# Z05_CC_SHIELD_02.net
KiCad netlist of a schematic drawn in EAGLE
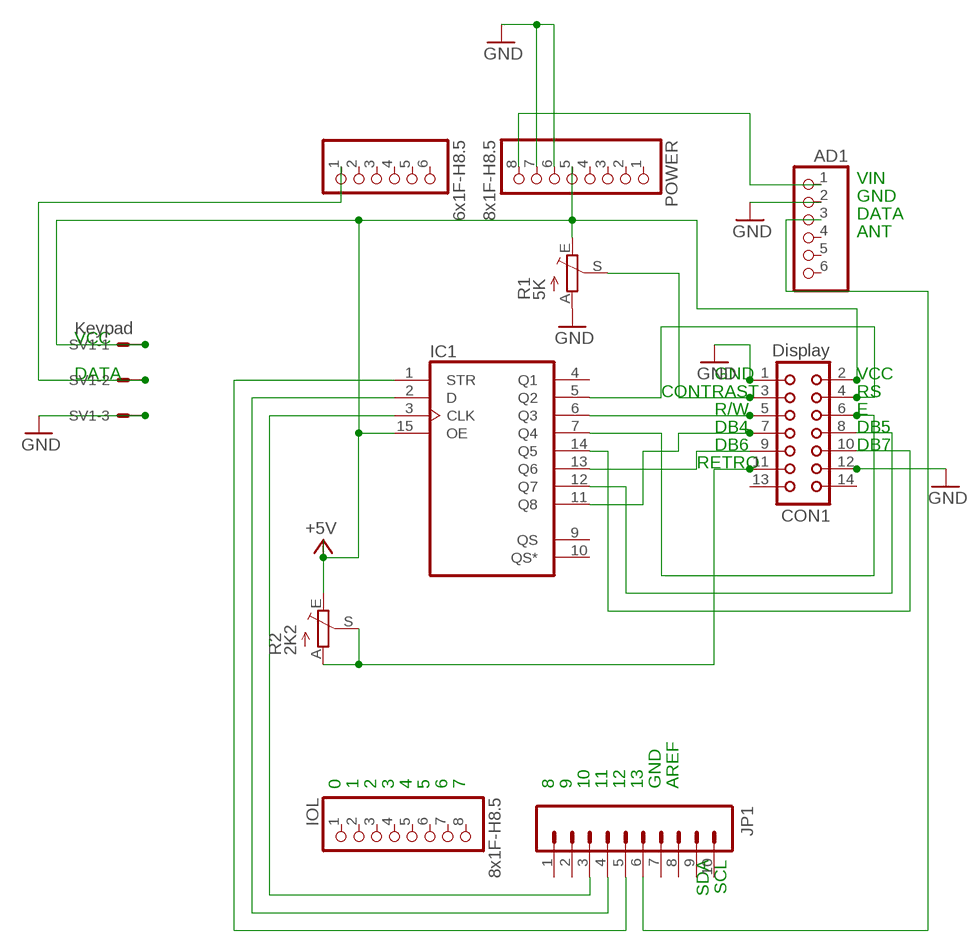
[diagram p0: schematic, sheet 1]

(export (version "E")
  (design (tool "Eeschema 10.0.6"))
  (components
    (comp (ref "AD")
      (value "6x1F-H8.5")
      (footprint "eagle-import:1X06")
      (libsource (lib "eagle-import") (part "PINHD-1X6"))
    )
    (comp (ref "AD1")
      (value "6x1F-H8.5")
      (footprint "eagle-import:1X06")
      (libsource (lib "eagle-import") (part "PINHD-1X6"))
    )
    (comp (ref "CON1")
      (value "Display")
      (footprint "eagle-import:CON14")
      (libsource (lib "eagle-import") (part "CON14"))
    )
    (comp (ref "IC1")
      (value "4094N")
      (footprint "eagle-import:DIL16")
      (libsource (lib "eagle-import") (part "4094N"))
    )
    (comp (ref "IOL")
      (value "8x1F-H8.5")
      (footprint "eagle-import:1X08")
      (libsource (lib "eagle-import") (part "PINHD-1X8"))
    )
    (comp (ref "JP1")
      (value "M10\"")
      (footprint "eagle-import:1X10")
      (libsource (lib "eagle-import") (part "M10{dblquote}"))
    )
    (comp (ref "POWER")
      (value "8x1F-H8.5")
      (footprint "eagle-import:1X08")
      (libsource (lib "eagle-import") (part "PINHD-1X8"))
    )
    (comp (ref "R1")
      (value "5K")
      (footprint "eagle-import:LI10")
      (libsource (lib "eagle-import") (part "TRIM_EU-LI10"))
    )
    (comp (ref "R2")
      (value "2K2")
      (footprint "eagle-import:LI10")
      (libsource (lib "eagle-import") (part "TRIM_EU-LI10"))
    )
    (comp (ref "SV1")
      (value "Keypad")
      (footprint "eagle-import:7395-05")
      (libsource (lib "eagle-import") (part "22-?-0505-7058"))
    )
  )
  (nets
    (net (code "1") (name "+5V") (class "Default")
      (node (ref "CON1") (pin "2") (pinfunction "2_2") (pintype "passive"))
      (node (ref "IC1") (pin "15") (pinfunction "OE_15") (pintype "input"))
      (node (ref "POWER") (pin "5") (pinfunction "5_5") (pintype "passive"))
      (node (ref "R1") (pin "E") (pinfunction "E_E") (pintype "passive"))
      (node (ref "R2") (pin "E") (pinfunction "E_E") (pintype "passive"))
      (node (ref "SV1") (pin "1") (pinfunction "S_1") (pintype "passive"))
    )
    (net (code "2") (name "GND") (class "Default")
      (node (ref "AD1") (pin "2") (pinfunction "2_2") (pintype "passive"))
      (node (ref "CON1") (pin "1") (pinfunction "1_1") (pintype "passive"))
      (node (ref "CON1") (pin "12") (pinfunction "12_12") (pintype "passive"))
      (node (ref "POWER") (pin "6") (pinfunction "6_6") (pintype "passive"))
      (node (ref "POWER") (pin "7") (pinfunction "7_7") (pintype "passive"))
      (node (ref "R1") (pin "A") (pinfunction "A_A") (pintype "passive"))
      (node (ref "SV1") (pin "3") (pinfunction "S_3") (pintype "passive"))
    )
    (net (code "3") (name "Net-(AD1-Pad1)") (class "Default")
      (node (ref "AD1") (pin "1") (pinfunction "1_1") (pintype "passive"))
      (node (ref "POWER") (pin "8") (pinfunction "8_8") (pintype "passive"))
    )
    (net (code "4") (name "Net-(AD1-Pad3)") (class "Default")
      (node (ref "AD1") (pin "3") (pinfunction "3_3") (pintype "passive"))
      (node (ref "JP1") (pin "6") (pinfunction "6_6") (pintype "passive"))
    )
    (net (code "5") (name "Net-(CON1-Pad3)") (class "Default")
      (node (ref "CON1") (pin "3") (pinfunction "3_3") (pintype "passive"))
      (node (ref "R1") (pin "S") (pinfunction "S_S") (pintype "passive"))
    )
    (net (code "6") (name "Net-(CON1-Pad11)") (class "Default")
      (node (ref "CON1") (pin "11") (pinfunction "11_11") (pintype "passive"))
      (node (ref "R2") (pin "A") (pinfunction "A_A") (pintype "passive"))
      (node (ref "R2") (pin "S") (pinfunction "S_S") (pintype "passive"))
    )
    (net (code "7") (name "Net-(IC1A-CLK)") (class "Default")
      (node (ref "IC1") (pin "3") (pinfunction "CLK_3") (pintype "input"))
      (node (ref "JP1") (pin "3") (pinfunction "3_3") (pintype "passive"))
    )
    (net (code "8") (name "Net-(IC1A-D)") (class "Default")
      (node (ref "IC1") (pin "2") (pinfunction "D_2") (pintype "input"))
      (node (ref "JP1") (pin "4") (pinfunction "4_4") (pintype "passive"))
    )
    (net (code "9") (name "Net-(IC1A-Q2)") (class "Default")
      (node (ref "CON1") (pin "4") (pinfunction "4_4") (pintype "passive"))
      (node (ref "IC1") (pin "5") (pinfunction "Q2_5") (pintype "output"))
    )
    (net (code "10") (name "Net-(IC1A-Q3)") (class "Default")
      (node (ref "CON1") (pin "5") (pinfunction "5_5") (pintype "passive"))
      (node (ref "IC1") (pin "6") (pinfunction "Q3_6") (pintype "output"))
    )
    (net (code "11") (name "Net-(IC1A-Q4)") (class "Default")
      (node (ref "CON1") (pin "6") (pinfunction "6_6") (pintype "passive"))
      (node (ref "IC1") (pin "7") (pinfunction "Q4_7") (pintype "output"))
    )
    (net (code "12") (name "Net-(IC1A-Q5)") (class "Default")
      (node (ref "CON1") (pin "10") (pinfunction "10_10") (pintype "passive"))
      (node (ref "IC1") (pin "14") (pinfunction "Q5_14") (pintype "output"))
    )
    (net (code "13") (name "Net-(IC1A-Q6)") (class "Default")
      (node (ref "CON1") (pin "9") (pinfunction "9_9") (pintype "passive"))
      (node (ref "IC1") (pin "13") (pinfunction "Q6_13") (pintype "output"))
    )
    (net (code "14") (name "Net-(IC1A-Q7)") (class "Default")
      (node (ref "CON1") (pin "8") (pinfunction "8_8") (pintype "passive"))
      (node (ref "IC1") (pin "12") (pinfunction "Q7_12") (pintype "output"))
    )
    (net (code "15") (name "Net-(IC1A-Q8)") (class "Default")
      (node (ref "CON1") (pin "7") (pinfunction "7_7") (pintype "passive"))
      (node (ref "IC1") (pin "11") (pinfunction "Q8_11") (pintype "output"))
    )
    (net (code "16") (name "Net-(IC1A-STR)") (class "Default")
      (node (ref "IC1") (pin "1") (pinfunction "STR_1") (pintype "input"))
      (node (ref "JP1") (pin "5") (pinfunction "5_5") (pintype "passive"))
    )
    (net (code "17") (name "Net-(SV1B-S)") (class "Default")
      (node (ref "AD") (pin "1") (pinfunction "1_1") (pintype "passive"))
      (node (ref "SV1") (pin "2") (pinfunction "S_2") (pintype "passive"))
    )
    (net (code "18") (name "unconnected-(AD-Pad2)") (class "Default")
      (node (ref "AD") (pin "2") (pinfunction "2_2") (pintype "passive"))
    )
    (net (code "19") (name "unconnected-(AD-Pad3)") (class "Default")
      (node (ref "AD") (pin "3") (pinfunction "3_3") (pintype "passive"))
    )
    (net (code "20") (name "unconnected-(AD-Pad4)") (class "Default")
      (node (ref "AD") (pin "4") (pinfunction "4_4") (pintype "passive"))
    )
    (net (code "21") (name "unconnected-(AD-Pad5)") (class "Default")
      (node (ref "AD") (pin "5") (pinfunction "5_5") (pintype "passive"))
    )
    (net (code "22") (name "unconnected-(AD-Pad6)") (class "Default")
      (node (ref "AD") (pin "6") (pinfunction "6_6") (pintype "passive"))
    )
    (net (code "23") (name "unconnected-(AD1-Pad4)") (class "Default")
      (node (ref "AD1") (pin "4") (pinfunction "4_4") (pintype "passive"))
    )
    (net (code "24") (name "unconnected-(AD1-Pad5)") (class "Default")
      (node (ref "AD1") (pin "5") (pinfunction "5_5") (pintype "passive"))
    )
    (net (code "25") (name "unconnected-(AD1-Pad6)") (class "Default")
      (node (ref "AD1") (pin "6") (pinfunction "6_6") (pintype "passive"))
    )
    (net (code "26") (name "unconnected-(CON1-Pad13)") (class "Default")
      (node (ref "CON1") (pin "13") (pinfunction "13_13") (pintype "passive"))
    )
    (net (code "27") (name "unconnected-(CON1-Pad14)") (class "Default")
      (node (ref "CON1") (pin "14") (pinfunction "14_14") (pintype "passive"))
    )
    (net (code "28") (name "unconnected-(IC1A-Q1-Pad4)") (class "Default")
      (node (ref "IC1") (pin "4") (pinfunction "Q1_4") (pintype "output"))
    )
    (net (code "29") (name "unconnected-(IC1A-QS*-Pad10)") (class "Default")
      (node (ref "IC1") (pin "10") (pinfunction "QS*_10") (pintype "output"))
    )
    (net (code "30") (name "unconnected-(IC1A-QS-Pad9)") (class "Default")
      (node (ref "IC1") (pin "9") (pinfunction "QS_9") (pintype "output"))
    )
    (net (code "31") (name "unconnected-(IOL-Pad1)") (class "Default")
      (node (ref "IOL") (pin "1") (pinfunction "1_1") (pintype "passive"))
    )
    (net (code "32") (name "unconnected-(IOL-Pad2)") (class "Default")
      (node (ref "IOL") (pin "2") (pinfunction "2_2") (pintype "passive"))
    )
    (net (code "33") (name "unconnected-(IOL-Pad3)") (class "Default")
      (node (ref "IOL") (pin "3") (pinfunction "3_3") (pintype "passive"))
    )
    (net (code "34") (name "unconnected-(IOL-Pad4)") (class "Default")
      (node (ref "IOL") (pin "4") (pinfunction "4_4") (pintype "passive"))
    )
    (net (code "35") (name "unconnected-(IOL-Pad5)") (class "Default")
      (node (ref "IOL") (pin "5") (pinfunction "5_5") (pintype "passive"))
    )
    (net (code "36") (name "unconnected-(IOL-Pad6)") (class "Default")
      (node (ref "IOL") (pin "6") (pinfunction "6_6") (pintype "passive"))
    )
    (net (code "37") (name "unconnected-(IOL-Pad7)") (class "Default")
      (node (ref "IOL") (pin "7") (pinfunction "7_7") (pintype "passive"))
    )
    (net (code "38") (name "unconnected-(IOL-Pad8)") (class "Default")
      (node (ref "IOL") (pin "8") (pinfunction "8_8") (pintype "passive"))
    )
    (net (code "39") (name "unconnected-(JP1-Pad1)") (class "Default")
      (node (ref "JP1") (pin "1") (pinfunction "1_1") (pintype "passive"))
    )
    (net (code "40") (name "unconnected-(JP1-Pad2)") (class "Default")
      (node (ref "JP1") (pin "2") (pinfunction "2_2") (pintype "passive"))
    )
    (net (code "41") (name "unconnected-(JP1-Pad7)") (class "Default")
      (node (ref "JP1") (pin "7") (pinfunction "7_7") (pintype "passive"))
    )
    (net (code "42") (name "unconnected-(JP1-Pad8)") (class "Default")
      (node (ref "JP1") (pin "8") (pinfunction "8_8") (pintype "passive"))
    )
    (net (code "43") (name "unconnected-(JP1-Pad9)") (class "Default")
      (node (ref "JP1") (pin "9") (pinfunction "9_9") (pintype "passive"))
    )
    (net (code "44") (name "unconnected-(JP1-Pad10)") (class "Default")
      (node (ref "JP1") (pin "10") (pinfunction "10_10") (pintype "passive"))
    )
    (net (code "45") (name "unconnected-(POWER-Pad1)") (class "Default")
      (node (ref "POWER") (pin "1") (pinfunction "1_1") (pintype "passive"))
    )
    (net (code "46") (name "unconnected-(POWER-Pad2)") (class "Default")
      (node (ref "POWER") (pin "2") (pinfunction "2_2") (pintype "passive"))
    )
    (net (code "47") (name "unconnected-(POWER-Pad3)") (class "Default")
      (node (ref "POWER") (pin "3") (pinfunction "3_3") (pintype "passive"))
    )
    (net (code "48") (name "unconnected-(POWER-Pad4)") (class "Default")
      (node (ref "POWER") (pin "4") (pinfunction "4_4") (pintype "passive"))
    )
  )
)
